# ProDocument_Original_2023-07-23.net
KiCad netlist of a schematic drawn in EasyEDA Pro
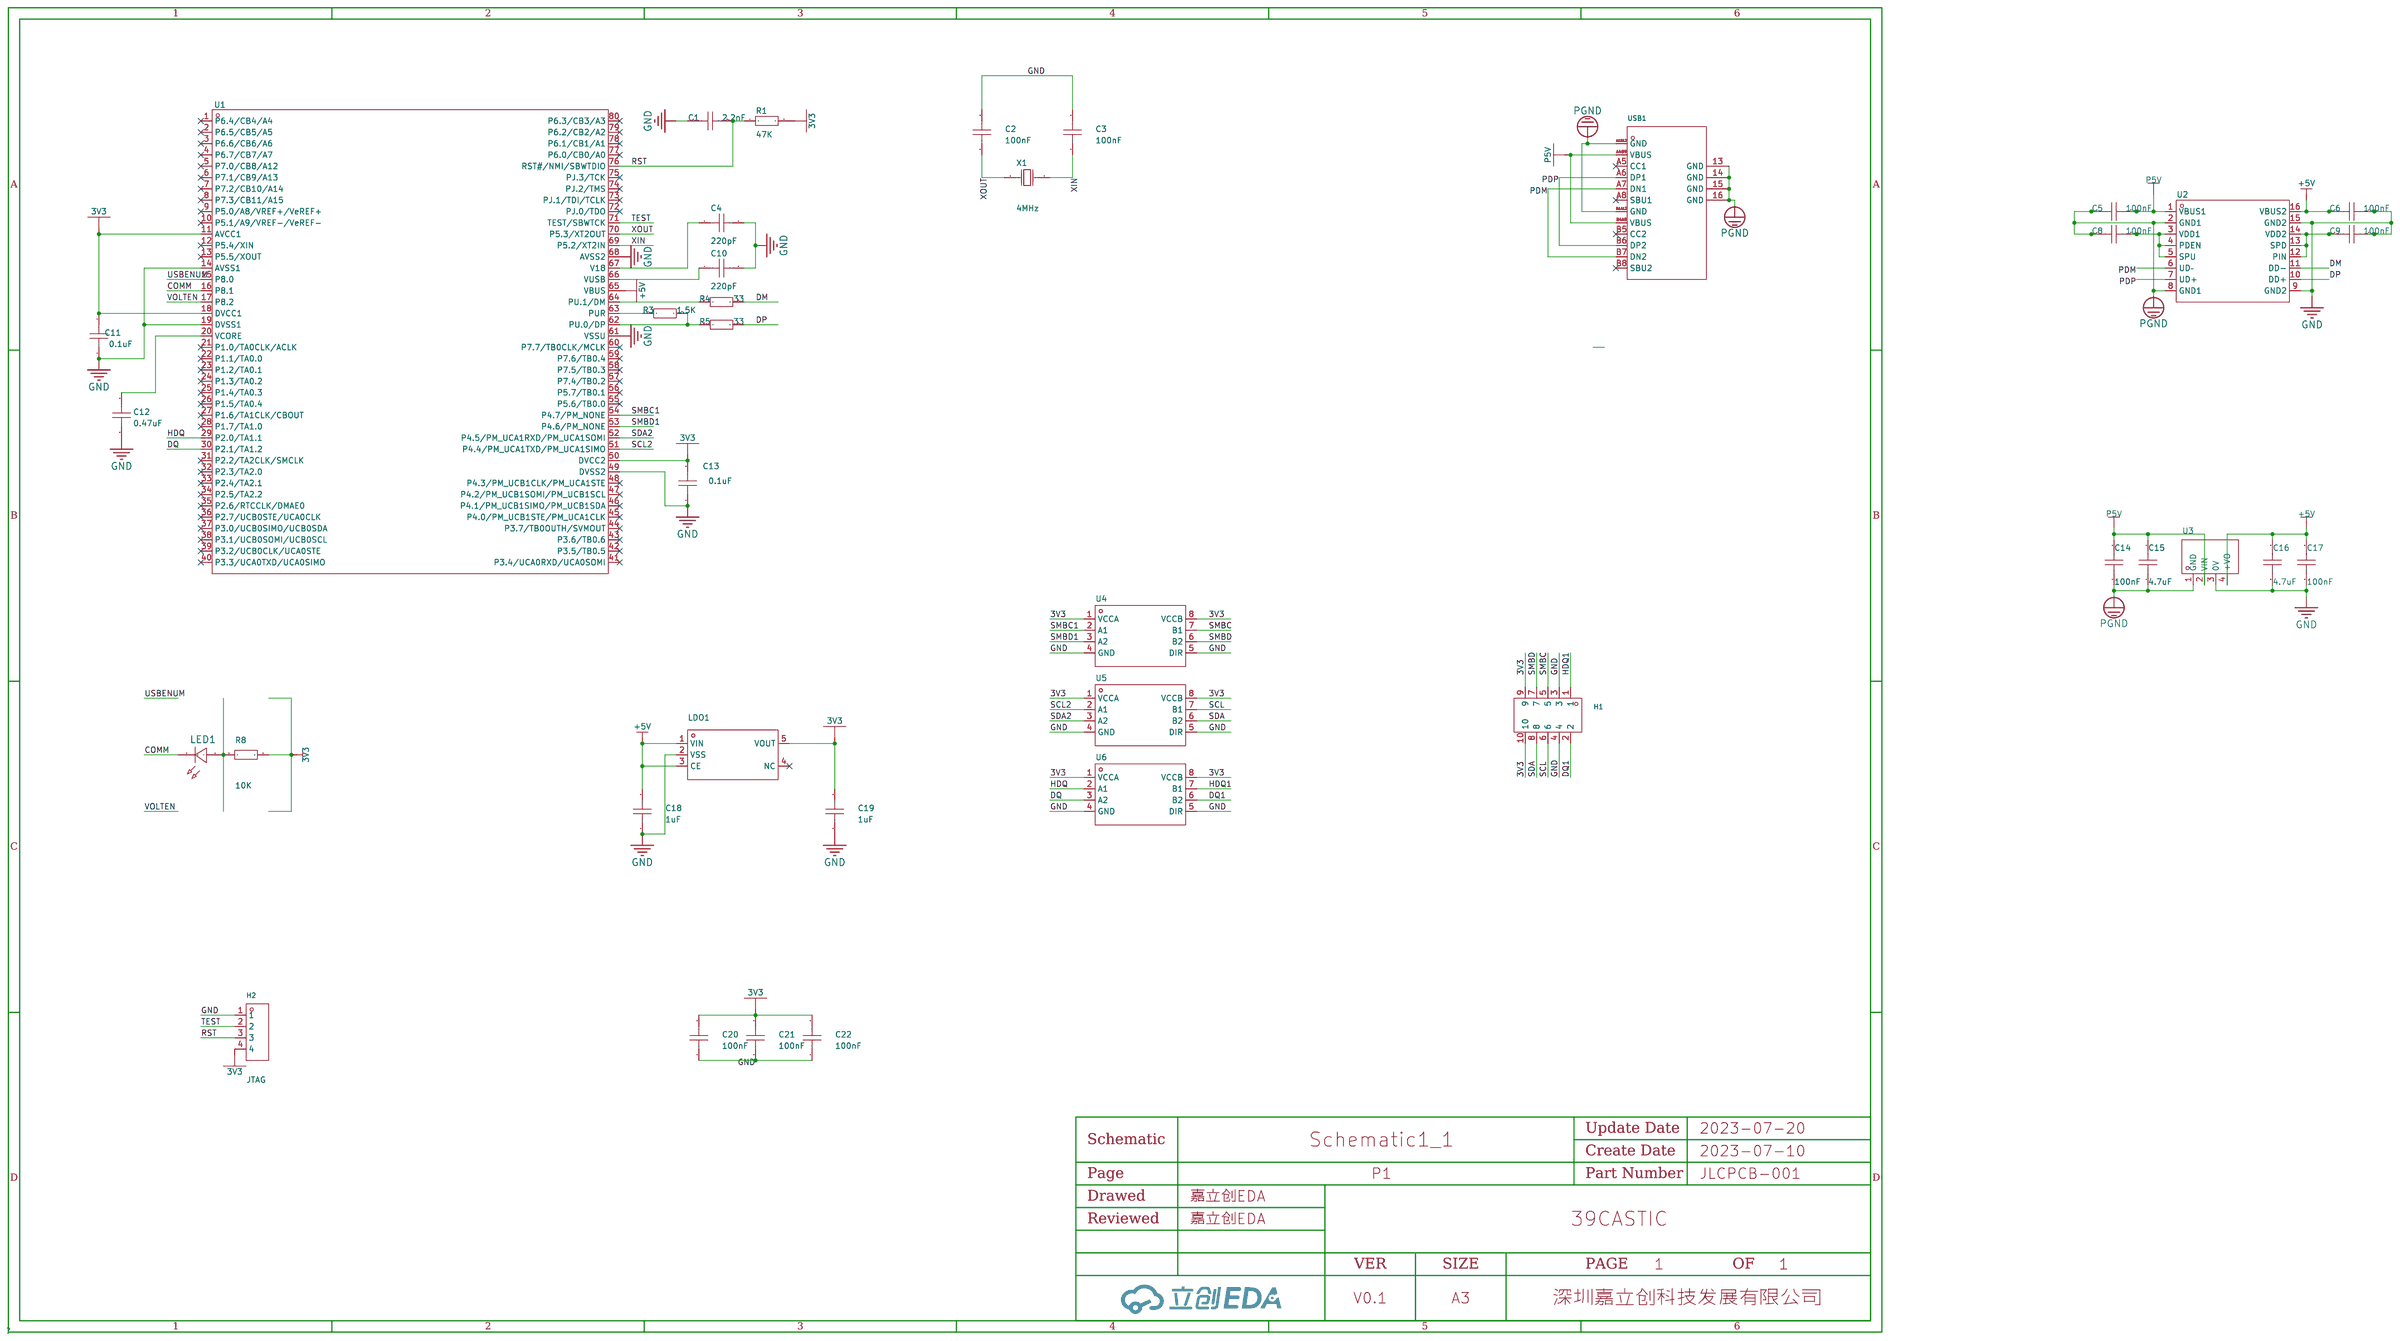
[diagram p0: schematic sheet]

(export (version "E")
  (design (tool "Eeschema 10.0.6"))
  (components
    (comp (ref "C1")
      (value "2.2nF")
      (footprint "easyedapro:C0603_1")
      (description "容值:100nF;精度:±10%;额定电压:50V;温度系数:X7R;")
      (libsource (lib "easyedapro") (part "C1210X7R475K630NT"))
    )
    (comp (ref "C2")
      (value "100nF")
      (footprint "easyedapro:C0603")
      (libsource (lib "easyedapro") (part "CapAcitance"))
    )
    (comp (ref "C3")
      (value "100nF")
      (footprint "easyedapro:C0603")
      (libsource (lib "easyedapro") (part "CapAcitance"))
    )
    (comp (ref "C4")
      (value "220pF")
      (footprint "easyedapro:C0603_1")
      (description "容值:100nF;精度:±10%;额定电压:50V;温度系数:X7R;")
      (libsource (lib "easyedapro") (part "C1210X7R475K630NT"))
    )
    (comp (ref "C5")
      (value "100nF")
      (footprint "easyedapro:C0603")
      (libsource (lib "easyedapro") (part "CapAcitance"))
    )
    (comp (ref "C6")
      (value "100nF")
      (footprint "easyedapro:C0603")
      (libsource (lib "easyedapro") (part "CapAcitance"))
    )
    (comp (ref "C8")
      (value "100nF")
      (footprint "easyedapro:C0603")
      (libsource (lib "easyedapro") (part "CapAcitance"))
    )
    (comp (ref "C9")
      (value "100nF")
      (footprint "easyedapro:C0603")
      (libsource (lib "easyedapro") (part "CapAcitance"))
    )
    (comp (ref "C10")
      (value "220pF")
      (footprint "easyedapro:C0603_1")
      (description "容值:100nF;精度:±10%;额定电压:50V;温度系数:X7R;")
      (libsource (lib "easyedapro") (part "C1210X7R475K630NT"))
    )
    (comp (ref "C11")
      (value "0.1uF")
      (footprint "easyedapro:C0603_1")
      (description "容值:100nF;精度:±10%;额定电压:50V;温度系数:X7R;")
      (libsource (lib "easyedapro") (part "C1210X7R475K630NT"))
    )
    (comp (ref "C12")
      (value "0.47uF")
      (footprint "easyedapro:C0603_1")
      (description "容值:100nF;精度:±10%;额定电压:50V;温度系数:X7R;")
      (libsource (lib "easyedapro") (part "C1210X7R475K630NT"))
    )
    (comp (ref "C13")
      (value "0.1uF")
      (footprint "easyedapro:C0603_1")
      (description "容值:100nF;精度:±10%;额定电压:50V;温度系数:X7R;")
      (libsource (lib "easyedapro") (part "C1210X7R475K630NT"))
    )
    (comp (ref "C14")
      (value "100nF")
      (footprint "easyedapro:C0603")
      (libsource (lib "easyedapro") (part "CapAcitance"))
    )
    (comp (ref "C15")
      (value "4.7uF")
      (footprint "easyedapro:C0603")
      (libsource (lib "easyedapro") (part "CapAcitance"))
    )
    (comp (ref "C16")
      (value "4.7uF")
      (footprint "easyedapro:C0603")
      (libsource (lib "easyedapro") (part "CapAcitance"))
    )
    (comp (ref "C17")
      (value "100nF")
      (footprint "easyedapro:C0603")
      (libsource (lib "easyedapro") (part "CapAcitance"))
    )
    (comp (ref "C18")
      (value "1uF")
      (footprint "easyedapro:C0603")
      (libsource (lib "easyedapro") (part "CapAcitance"))
    )
    (comp (ref "C19")
      (value "1uF")
      (footprint "easyedapro:C0603")
      (libsource (lib "easyedapro") (part "CapAcitance"))
    )
    (comp (ref "C20")
      (value "100nF")
      (footprint "easyedapro:C0603")
      (libsource (lib "easyedapro") (part "CapAcitance"))
    )
    (comp (ref "C21")
      (value "100nF")
      (footprint "easyedapro:C0603")
      (libsource (lib "easyedapro") (part "CapAcitance"))
    )
    (comp (ref "C22")
      (value "100nF")
      (footprint "easyedapro:C0603")
      (libsource (lib "easyedapro") (part "CapAcitance"))
    )
    (comp (ref "H1")
      (value "PZ254V-12-10P")
      (footprint "easyedapro:HDR-TH_10P-P2.54-V-M-R2-C5-S2.54")
      (fields (field (name "Manufacturer") "XFCN(兴飞)"))
      (libsource (lib "easyedapro") (part "PZ254V-12-10P"))
    )
    (comp (ref "H2")
      (value "JTAG")
      (footprint "easyedapro:HDR-TH_4P-P2.54-V-F")
      (libsource (lib "easyedapro") (part "2.54-1*4P母"))
    )
    (comp (ref "LDO1")
      (value "ME6211C33M5G-N")
      (footprint "easyedapro:SOT-23-5_L3.0-W1.7-P0.95-LS2.8-BL")
      (description "输出类型:固定;输出极性:正;最大输入电压:6V;输出电压:3.3V;输出电流:500mA;电源纹波抑制比(PSRR):70dB;")
      (fields (field (name "Manufacturer") "MICRONE(南京微盟)"))
      (libsource (lib "easyedapro") (part "ME6211C33M5G-N"))
    )
    (comp (ref "LED1")
      (value "~")
      (footprint "easyedapro:LED_0603")
      (libsource (lib "easyedapro") (part "LED_R"))
    )
    (comp (ref "R1")
      (value "47K")
      (footprint "easyedapro:R0603_1")
      (libsource (lib "easyedapro") (part "电阻_1"))
    )
    (comp (ref "R3")
      (value "1.5K")
      (footprint "easyedapro:R0603_1")
      (libsource (lib "easyedapro") (part "电阻_1"))
    )
    (comp (ref "R4")
      (value "33")
      (footprint "easyedapro:R0603_1")
      (libsource (lib "easyedapro") (part "电阻_1"))
    )
    (comp (ref "R5")
      (value "33")
      (footprint "easyedapro:R0603_1")
      (libsource (lib "easyedapro") (part "电阻_1"))
    )
    (comp (ref "R8") (value "10K") (footprint "easyedapro:R0603") (libsource (lib "easyedapro") (part "电阻")))
    (comp (ref "U1")
      (value "~")
      (footprint "easyedapro:LQFP-80_L12.0-W12.0-P0.50-LS14.0-BL")
      (description "CPU位数:-;ROM类型:-;CPU内核:-;主频（MAX):-;工作电压:-;")
      (fields (field (name "Manufacturer Part") "MSP430F5529IPN") (field (name "Manufacturer") "TI(德州仪器)"))
      (libsource (lib "easyedapro") (part "MSP430F5529IPN"))
    )
    (comp (ref "U2")
      (value "ADUM3160BRWZ-RL")
      (footprint "easyedapro:SOIC-16_L10.3-W7.5-P1.27-LS10.3-BL")
      (description "隔离器的技术构架:-;类型:-;通道数:-;通道类型:-;隔离电压:-;数据速率:-;")
      (fields (field (name "Manufacturer") "ADI(亚德诺)/LINEAR(凌特)"))
      (libsource (lib "easyedapro") (part "ADUM3160BRWZ-RL"))
    )
    (comp (ref "U3")
      (value "B0505S-1W")
      (footprint "easyedapro:PWRM-TH_B0505S-1W")
      (description "电压输出的组数:1;最大输入电压:5.5V;输出电压:5V;输出电流（最大值/满载）:200mA;")
      (fields (field (name "Manufacturer") "德旭电子(DEXU)"))
      (libsource (lib "easyedapro") (part "B0505S-1W_C2912568"))
    )
    (comp (ref "U4")
      (value "SN74LVC2T45DCUR")
      (footprint "easyedapro:VSSOP-8_L2.4-W2.1-P0.50-LS3.2-BR")
      (description "SN74LVC2T45 具有可配置电压转换和三态输出的 2 位双电源总线收发器")
      (fields (field (name "Manufacturer") "TI(德州仪器)"))
      (libsource (lib "easyedapro") (part "SN74LVC2T45DCUR"))
    )
    (comp (ref "U5")
      (value "SN74LVC2T45DCUR")
      (footprint "easyedapro:VSSOP-8_L2.4-W2.1-P0.50-LS3.2-BR")
      (description "SN74LVC2T45 具有可配置电压转换和三态输出的 2 位双电源总线收发器")
      (fields (field (name "Manufacturer") "TI(德州仪器)"))
      (libsource (lib "easyedapro") (part "SN74LVC2T45DCUR"))
    )
    (comp (ref "U6")
      (value "SN74LVC2T45DCUR")
      (footprint "easyedapro:VSSOP-8_L2.4-W2.1-P0.50-LS3.2-BR")
      (description "SN74LVC2T45 具有可配置电压转换和三态输出的 2 位双电源总线收发器")
      (fields (field (name "Manufacturer") "TI(德州仪器)"))
      (libsource (lib "easyedapro") (part "SN74LVC2T45DCUR"))
    )
    (comp (ref "USB1")
      (value "TYPEC-304-BCP16")
      (footprint "easyedapro:USB-C-SMD_TYPEC-304-BCP16")
      (fields (field (name "Manufacturer") "XUNPU(讯普)"))
      (libsource (lib "easyedapro") (part "TYPEC-304-BCP16"))
    )
    (comp (ref "X1")
      (value "4MHz")
      (footprint "easyedapro:HC-49US_L11.5-W4.5-P4.88")
      (description "频率:4MHz;频率公差:±20ppm;负载电容:20pF;")
      (fields (field (name "Manufacturer Part") "X49SD4MSD2SC") (field (name "Manufacturer") "YXC(扬兴晶振)"))
      (libsource (lib "easyedapro") (part "X49SD4MSD2SC"))
    )
  )
  (nets
    (net (code "1") (name "+5V") (class "Default")
      (node (ref "C16") (pin "2") (pinfunction "2_2") (pintype "input"))
      (node (ref "C17") (pin "2") (pinfunction "2_2") (pintype "input"))
      (node (ref "C18") (pin "2") (pinfunction "2_2") (pintype "input"))
      (node (ref "C6") (pin "1") (pinfunction "1_1") (pintype "input"))
      (node (ref "LDO1") (pin "1") (pinfunction "VIN_1") (pintype "input"))
      (node (ref "LDO1") (pin "3") (pinfunction "CE_3") (pintype "input"))
      (node (ref "U1") (pin "65") (pinfunction "VBUS_65") (pintype "input"))
      (node (ref "U2") (pin "16") (pinfunction "VBUS2_16") (pintype "input"))
      (node (ref "U3") (pin "4") (pinfunction "+VO_4") (pintype "input"))
    )
    (net (code "2") (name "/COMM") (class "Default")
      (node (ref "LED1") (pin "1") (pinfunction "C_1") (pintype "input"))
      (node (ref "U1") (pin "16") (pinfunction "P8.1_16") (pintype "input"))
    )
    (net (code "3") (name "/DM") (class "Default")
      (node (ref "R4") (pin "2") (pinfunction "2_2") (pintype "input"))
      (node (ref "U2") (pin "11") (pinfunction "DD-_11") (pintype "input"))
    )
    (net (code "4") (name "/DP") (class "Default")
      (node (ref "R5") (pin "2") (pinfunction "2_2") (pintype "input"))
      (node (ref "U2") (pin "10") (pinfunction "DD+_10") (pintype "input"))
    )
    (net (code "5") (name "/DQ") (class "Default")
      (node (ref "U1") (pin "30") (pinfunction "P2.1/TA1.2_30") (pintype "input"))
      (node (ref "U6") (pin "3") (pinfunction "A2_3") (pintype "input"))
    )
    (net (code "6") (name "/DQ1") (class "Default")
      (node (ref "H1") (pin "2") (pinfunction "2_2") (pintype "input"))
      (node (ref "U6") (pin "6") (pinfunction "B2_6") (pintype "input"))
    )
    (net (code "7") (name "/HDQ") (class "Default")
      (node (ref "U1") (pin "29") (pinfunction "P2.0/TA1.1_29") (pintype "input"))
      (node (ref "U6") (pin "2") (pinfunction "A1_2") (pintype "input"))
    )
    (net (code "8") (name "/HDQ1") (class "Default")
      (node (ref "H1") (pin "1") (pinfunction "1_1") (pintype "input"))
      (node (ref "U6") (pin "7") (pinfunction "B1_7") (pintype "input"))
    )
    (net (code "9") (name "/PDM") (class "Default")
      (node (ref "U2") (pin "6") (pinfunction "UD–_6") (pintype "input"))
      (node (ref "USB1") (pin "A7") (pinfunction "DN1_A7") (pintype "input"))
      (node (ref "USB1") (pin "B7") (pinfunction "DN2_B7") (pintype "input"))
    )
    (net (code "10") (name "/PDP") (class "Default")
      (node (ref "U2") (pin "7") (pinfunction "UD+_7") (pintype "input"))
      (node (ref "USB1") (pin "A6") (pinfunction "DP1_A6") (pintype "input"))
      (node (ref "USB1") (pin "B6") (pinfunction "DP2_B6") (pintype "input"))
    )
    (net (code "11") (name "/RST") (class "Default")
      (node (ref "C1") (pin "2") (pinfunction "2_2") (pintype "input"))
      (node (ref "H2") (pin "3") (pinfunction "3_3") (pintype "input"))
      (node (ref "R1") (pin "1") (pinfunction "1_1") (pintype "input"))
      (node (ref "U1") (pin "76") (pinfunction "RST#/NMI/SBWTDIO_76") (pintype "input"))
    )
    (net (code "12") (name "/SCL") (class "Default")
      (node (ref "H1") (pin "6") (pinfunction "6_6") (pintype "input"))
      (node (ref "U5") (pin "7") (pinfunction "B1_7") (pintype "input"))
    )
    (net (code "13") (name "/SCL2") (class "Default")
      (node (ref "U1") (pin "51") (pinfunction "P4.4/PM_UCA1TXD/PM_UCA1SIMO_51") (pintype "input"))
      (node (ref "U5") (pin "2") (pinfunction "A1_2") (pintype "input"))
    )
    (net (code "14") (name "/SDA") (class "Default")
      (node (ref "H1") (pin "8") (pinfunction "8_8") (pintype "input"))
      (node (ref "U5") (pin "6") (pinfunction "B2_6") (pintype "input"))
    )
    (net (code "15") (name "/SDA2") (class "Default")
      (node (ref "U1") (pin "52") (pinfunction "P4.5/PM_UCA1RXD/PM_UCA1SOMI_52") (pintype "input"))
      (node (ref "U5") (pin "3") (pinfunction "A2_3") (pintype "input"))
    )
    (net (code "16") (name "/SMBC") (class "Default")
      (node (ref "H1") (pin "5") (pinfunction "5_5") (pintype "input"))
      (node (ref "U4") (pin "7") (pinfunction "B1_7") (pintype "input"))
    )
    (net (code "17") (name "/SMBC1") (class "Default")
      (node (ref "U1") (pin "54") (pinfunction "P4.7/PM_NONE_54") (pintype "input"))
      (node (ref "U4") (pin "2") (pinfunction "A1_2") (pintype "input"))
    )
    (net (code "18") (name "/SMBD") (class "Default")
      (node (ref "H1") (pin "7") (pinfunction "7_7") (pintype "input"))
      (node (ref "U4") (pin "6") (pinfunction "B2_6") (pintype "input"))
    )
    (net (code "19") (name "/SMBD1") (class "Default")
      (node (ref "U1") (pin "53") (pinfunction "P4.6/PM_NONE_53") (pintype "input"))
      (node (ref "U4") (pin "3") (pinfunction "A2_3") (pintype "input"))
    )
    (net (code "20") (name "/TEST") (class "Default")
      (node (ref "H2") (pin "2") (pinfunction "2_2") (pintype "input"))
      (node (ref "U1") (pin "71") (pinfunction "TEST/SBWTCK_71") (pintype "input"))
    )
    (net (code "21") (name "/USBENUM") (class "Default")
      (node (ref "U1") (pin "15") (pinfunction "P8.0_15") (pintype "input"))
    )
    (net (code "22") (name "/VOLTEN") (class "Default")
      (node (ref "U1") (pin "17") (pinfunction "P8.2_17") (pintype "input"))
    )
    (net (code "23") (name "/XIN") (class "Default")
      (node (ref "C3") (pin "1") (pinfunction "1_1") (pintype "input"))
      (node (ref "U1") (pin "69") (pinfunction "P5.2/XT2IN_69") (pintype "input"))
      (node (ref "X1") (pin "1") (pinfunction "OSC1_1") (pintype "input"))
    )
    (net (code "24") (name "/XOUT") (class "Default")
      (node (ref "C2") (pin "1") (pinfunction "1_1") (pintype "input"))
      (node (ref "U1") (pin "70") (pinfunction "P5.3/XT2OUT_70") (pintype "input"))
      (node (ref "X1") (pin "2") (pinfunction "OSC2_2") (pintype "input"))
    )
    (net (code "25") (name "3V3") (class "Default")
      (node (ref "C11") (pin "2") (pinfunction "2_2") (pintype "input"))
      (node (ref "C13") (pin "2") (pinfunction "2_2") (pintype "input"))
      (node (ref "C19") (pin "2") (pinfunction "2_2") (pintype "input"))
      (node (ref "C20") (pin "2") (pinfunction "2_2") (pintype "input"))
      (node (ref "C21") (pin "2") (pinfunction "2_2") (pintype "input"))
      (node (ref "C22") (pin "2") (pinfunction "2_2") (pintype "input"))
      (node (ref "H1") (pin "10") (pinfunction "10_10") (pintype "input"))
      (node (ref "H1") (pin "9") (pinfunction "9_9") (pintype "input"))
      (node (ref "H2") (pin "4") (pinfunction "4_4") (pintype "input"))
      (node (ref "LDO1") (pin "5") (pinfunction "VOUT_5") (pintype "input"))
      (node (ref "R1") (pin "2") (pinfunction "2_2") (pintype "input"))
      (node (ref "R8") (pin "2") (pinfunction "2_2") (pintype "input"))
      (node (ref "U1") (pin "11") (pinfunction "AVCC1_11") (pintype "input"))
      (node (ref "U1") (pin "18") (pinfunction "DVCC1_18") (pintype "input"))
      (node (ref "U1") (pin "50") (pinfunction "DVCC2_50") (pintype "input"))
      (node (ref "U4") (pin "1") (pinfunction "VCCA_1") (pintype "input"))
      (node (ref "U4") (pin "8") (pinfunction "VCCB_8") (pintype "input"))
      (node (ref "U5") (pin "1") (pinfunction "VCCA_1") (pintype "input"))
      (node (ref "U5") (pin "8") (pinfunction "VCCB_8") (pintype "input"))
      (node (ref "U6") (pin "1") (pinfunction "VCCA_1") (pintype "input"))
      (node (ref "U6") (pin "8") (pinfunction "VCCB_8") (pintype "input"))
    )
    (net (code "26") (name "GND") (class "Default")
      (node (ref "C1") (pin "1") (pinfunction "1_1") (pintype "input"))
      (node (ref "C10") (pin "2") (pinfunction "2_2") (pintype "input"))
      (node (ref "C11") (pin "1") (pinfunction "1_1") (pintype "input"))
      (node (ref "C12") (pin "1") (pinfunction "1_1") (pintype "input"))
      (node (ref "C13") (pin "1") (pinfunction "1_1") (pintype "input"))
      (node (ref "C16") (pin "1") (pinfunction "1_1") (pintype "input"))
      (node (ref "C17") (pin "1") (pinfunction "1_1") (pintype "input"))
      (node (ref "C18") (pin "1") (pinfunction "1_1") (pintype "input"))
      (node (ref "C19") (pin "1") (pinfunction "1_1") (pintype "input"))
      (node (ref "C2") (pin "2") (pinfunction "2_2") (pintype "input"))
      (node (ref "C20") (pin "1") (pinfunction "1_1") (pintype "input"))
      (node (ref "C21") (pin "1") (pinfunction "1_1") (pintype "input"))
      (node (ref "C22") (pin "1") (pinfunction "1_1") (pintype "input"))
      (node (ref "C3") (pin "2") (pinfunction "2_2") (pintype "input"))
      (node (ref "C4") (pin "2") (pinfunction "2_2") (pintype "input"))
      (node (ref "C6") (pin "2") (pinfunction "2_2") (pintype "input"))
      (node (ref "C9") (pin "2") (pinfunction "2_2") (pintype "input"))
      (node (ref "H1") (pin "3") (pinfunction "3_3") (pintype "input"))
      (node (ref "H1") (pin "4") (pinfunction "4_4") (pintype "input"))
      (node (ref "H2") (pin "1") (pinfunction "1_1") (pintype "input"))
      (node (ref "LDO1") (pin "2") (pinfunction "VSS_2") (pintype "input"))
      (node (ref "U1") (pin "14") (pinfunction "AVSS1_14") (pintype "input"))
      (node (ref "U1") (pin "19") (pinfunction "DVSS1_19") (pintype "input"))
      (node (ref "U1") (pin "49") (pinfunction "DVSS2_49") (pintype "input"))
      (node (ref "U1") (pin "61") (pinfunction "VSSU_61") (pintype "input"))
      (node (ref "U1") (pin "68") (pinfunction "AVSS2_68") (pintype "input"))
      (node (ref "U2") (pin "15") (pinfunction "GND2_15") (pintype "input"))
      (node (ref "U2") (pin "9") (pinfunction "GND2_9") (pintype "input"))
      (node (ref "U3") (pin "3") (pinfunction "0V_3") (pintype "input"))
      (node (ref "U4") (pin "4") (pinfunction "GND_4") (pintype "input"))
      (node (ref "U4") (pin "5") (pinfunction "DIR_5") (pintype "input"))
      (node (ref "U5") (pin "4") (pinfunction "GND_4") (pintype "input"))
      (node (ref "U5") (pin "5") (pinfunction "DIR_5") (pintype "input"))
      (node (ref "U6") (pin "4") (pinfunction "GND_4") (pintype "input"))
      (node (ref "U6") (pin "5") (pinfunction "DIR_5") (pintype "input"))
    )
    (net (code "27") (name "Net-(LED1-A)") (class "Default")
      (node (ref "LED1") (pin "2") (pinfunction "A_2") (pintype "input"))
      (node (ref "R8") (pin "1") (pinfunction "1_1") (pintype "input"))
    )
    (net (code "28") (name "Net-(U1-PU.0{slash}DP)") (class "Default")
      (node (ref "R3") (pin "2") (pinfunction "2_2") (pintype "input"))
      (node (ref "R5") (pin "1") (pinfunction "1_1") (pintype "input"))
      (node (ref "U1") (pin "62") (pinfunction "PU.0/DP_62") (pintype "input"))
    )
    (net (code "29") (name "Net-(U1-PU.1{slash}DM)") (class "Default")
      (node (ref "R4") (pin "1") (pinfunction "1_1") (pintype "input"))
      (node (ref "U1") (pin "64") (pinfunction "PU.1/DM_64") (pintype "input"))
    )
    (net (code "30") (name "Net-(U1-PUR)") (class "Default")
      (node (ref "R3") (pin "1") (pinfunction "1_1") (pintype "input"))
      (node (ref "U1") (pin "63") (pinfunction "PUR_63") (pintype "input"))
    )
    (net (code "31") (name "Net-(U1-V18)") (class "Default")
      (node (ref "C4") (pin "1") (pinfunction "1_1") (pintype "input"))
      (node (ref "U1") (pin "67") (pinfunction "V18_67") (pintype "input"))
    )
    (net (code "32") (name "Net-(U1-VCORE)") (class "Default")
      (node (ref "C12") (pin "2") (pinfunction "2_2") (pintype "input"))
      (node (ref "U1") (pin "20") (pinfunction "VCORE_20") (pintype "input"))
    )
    (net (code "33") (name "Net-(U1-VUSB)") (class "Default")
      (node (ref "C10") (pin "1") (pinfunction "1_1") (pintype "input"))
      (node (ref "U1") (pin "66") (pinfunction "VUSB_66") (pintype "input"))
    )
    (net (code "34") (name "Net-(U2-PDEN)") (class "Default")
      (node (ref "C8") (pin "2") (pinfunction "2_2") (pintype "input"))
      (node (ref "U2") (pin "3") (pinfunction "VDD1_3") (pintype "input"))
      (node (ref "U2") (pin "4") (pinfunction "PDEN_4") (pintype "input"))
      (node (ref "U2") (pin "5") (pinfunction "SPU_5") (pintype "input"))
    )
    (net (code "35") (name "Net-(U2-PIN)") (class "Default")
      (node (ref "C9") (pin "1") (pinfunction "1_1") (pintype "input"))
      (node (ref "U2") (pin "12") (pinfunction "PIN_12") (pintype "input"))
      (node (ref "U2") (pin "13") (pinfunction "SPD_13") (pintype "input"))
      (node (ref "U2") (pin "14") (pinfunction "VDD2_14") (pintype "input"))
    )
    (net (code "36") (name "P5V") (class "Default")
      (node (ref "C14") (pin "2") (pinfunction "2_2") (pintype "input"))
      (node (ref "C15") (pin "2") (pinfunction "2_2") (pintype "input"))
      (node (ref "C5") (pin "2") (pinfunction "2_2") (pintype "input"))
      (node (ref "U2") (pin "1") (pinfunction "VBUS1_1") (pintype "input"))
      (node (ref "U3") (pin "2") (pinfunction "VIN_2") (pintype "input"))
      (node (ref "USB1") (pin "A4B9") (pinfunction "VBUS_A4B9") (pintype "input"))
      (node (ref "USB1") (pin "B4A9") (pinfunction "VBUS_B4A9") (pintype "input"))
    )
    (net (code "37") (name "PGND") (class "Default")
      (node (ref "C14") (pin "1") (pinfunction "1_1") (pintype "input"))
      (node (ref "C15") (pin "1") (pinfunction "1_1") (pintype "input"))
      (node (ref "C5") (pin "1") (pinfunction "1_1") (pintype "input"))
      (node (ref "C8") (pin "1") (pinfunction "1_1") (pintype "input"))
      (node (ref "U2") (pin "2") (pinfunction "GND1_2") (pintype "input"))
      (node (ref "U2") (pin "8") (pinfunction "GND1_8") (pintype "input"))
      (node (ref "U3") (pin "1") (pinfunction "GND_1") (pintype "input"))
      (node (ref "USB1") (pin "13") (pinfunction "GND_13") (pintype "input"))
      (node (ref "USB1") (pin "14") (pinfunction "GND_14") (pintype "input"))
      (node (ref "USB1") (pin "15") (pinfunction "GND_15") (pintype "input"))
      (node (ref "USB1") (pin "16") (pinfunction "GND_16") (pintype "input"))
      (node (ref "USB1") (pin "A1B12") (pinfunction "GND_A1B12") (pintype "input"))
      (node (ref "USB1") (pin "B1A12") (pinfunction "GND_B1A12") (pintype "input"))
    )
    (net (code "38") (name "unconnected-(LDO1-NC-Pad4)") (class "Default")
      (node (ref "LDO1") (pin "4") (pinfunction "NC_4") (pintype "input+no_connect"))
    )
    (net (code "39") (name "unconnected-(U1-P1.0{slash}TA0CLK{slash}ACLK-Pad21)") (class "Default")
      (node (ref "U1") (pin "21") (pinfunction "P1.0/TA0CLK/ACLK_21") (pintype "input+no_connect"))
    )
    (net (code "40") (name "unconnected-(U1-P1.1{slash}TA0.0-Pad22)") (class "Default")
      (node (ref "U1") (pin "22") (pinfunction "P1.1/TA0.0_22") (pintype "input+no_connect"))
    )
    (net (code "41") (name "unconnected-(U1-P1.2{slash}TA0.1-Pad23)") (class "Default")
      (node (ref "U1") (pin "23") (pinfunction "P1.2/TA0.1_23") (pintype "input+no_connect"))
    )
    (net (code "42") (name "unconnected-(U1-P1.3{slash}TA0.2-Pad24)") (class "Default")
      (node (ref "U1") (pin "24") (pinfunction "P1.3/TA0.2_24") (pintype "input+no_connect"))
    )
    (net (code "43") (name "unconnected-(U1-P1.4{slash}TA0.3-Pad25)") (class "Default")
      (node (ref "U1") (pin "25") (pinfunction "P1.4/TA0.3_25") (pintype "input+no_connect"))
    )
    (net (code "44") (name "unconnected-(U1-P1.5{slash}TA0.4-Pad26)") (class "Default")
      (node (ref "U1") (pin "26") (pinfunction "P1.5/TA0.4_26") (pintype "input+no_connect"))
    )
    (net (code "45") (name "unconnected-(U1-P1.6{slash}TA1CLK{slash}CBOUT-Pad27)") (class "Default")
      (node (ref "U1") (pin "27") (pinfunction "P1.6/TA1CLK/CBOUT_27") (pintype "input+no_connect"))
    )
    (net (code "46") (name "unconnected-(U1-P1.7{slash}TA1.0-Pad28)") (class "Default")
      (node (ref "U1") (pin "28") (pinfunction "P1.7/TA1.0_28") (pintype "input+no_connect"))
    )
    (net (code "47") (name "unconnected-(U1-P2.2{slash}TA2CLK{slash}SMCLK-Pad31)") (class "Default")
      (node (ref "U1") (pin "31") (pinfunction "P2.2/TA2CLK/SMCLK_31") (pintype "input+no_connect"))
    )
    (net (code "48") (name "unconnected-(U1-P2.3{slash}TA2.0-Pad32)") (class "Default")
      (node (ref "U1") (pin "32") (pinfunction "P2.3/TA2.0_32") (pintype "input+no_connect"))
    )
    (net (code "49") (name "unconnected-(U1-P2.4{slash}TA2.1-Pad33)") (class "Default")
      (node (ref "U1") (pin "33") (pinfunction "P2.4/TA2.1_33") (pintype "input+no_connect"))
    )
    (net (code "50") (name "unconnected-(U1-P2.5{slash}TA2.2-Pad34)") (class "Default")
      (node (ref "U1") (pin "34") (pinfunction "P2.5/TA2.2_34") (pintype "input+no_connect"))
    )
    (net (code "51") (name "unconnected-(U1-P2.6{slash}RTCCLK{slash}DMAE0-Pad35)") (class "Default")
      (node (ref "U1") (pin "35") (pinfunction "P2.6/RTCCLK/DMAE0_35") (pintype "input+no_connect"))
    )
    (net (code "52") (name "unconnected-(U1-P2.7{slash}UCB0STE{slash}UCA0CLK-Pad36)") (class "Default")
      (node (ref "U1") (pin "36") (pinfunction "P2.7/UCB0STE/UCA0CLK_36") (pintype "input+no_connect"))
    )
    (net (code "53") (name "unconnected-(U1-P3.0{slash}UCB0SIMO{slash}UCB0SDA-Pad37)") (class "Default")
      (node (ref "U1") (pin "37") (pinfunction "P3.0/UCB0SIMO/UCB0SDA_37") (pintype "input+no_connect"))
    )
    (net (code "54") (name "unconnected-(U1-P3.1{slash}UCB0SOMI{slash}UCB0SCL-Pad38)") (class "Default")
      (node (ref "U1") (pin "38") (pinfunction "P3.1/UCB0SOMI/UCB0SCL_38") (pintype "input+no_connect"))
    )
    (net (code "55") (name "unconnected-(U1-P3.2{slash}UCB0CLK{slash}UCA0STE-Pad39)") (class "Default")
      (node (ref "U1") (pin "39") (pinfunction "P3.2/UCB0CLK/UCA0STE_39") (pintype "input+no_connect"))
    )
    (net (code "56") (name "unconnected-(U1-P3.3{slash}UCA0TXD{slash}UCA0SIMO-Pad40)") (class "Default")
      (node (ref "U1") (pin "40") (pinfunction "P3.3/UCA0TXD/UCA0SIMO_40") (pintype "input+no_connect"))
    )
    (net (code "57") (name "unconnected-(U1-P3.4{slash}UCA0RXD{slash}UCA0SOMI-Pad41)") (class "Default")
      (node (ref "U1") (pin "41") (pinfunction "P3.4/UCA0RXD/UCA0SOMI_41") (pintype "input+no_connect"))
    )
    (net (code "58") (name "unconnected-(U1-P3.5{slash}TB0.5-Pad42)") (class "Default")
      (node (ref "U1") (pin "42") (pinfunction "P3.5/TB0.5_42") (pintype "input+no_connect"))
    )
    (net (code "59") (name "unconnected-(U1-P3.6{slash}TB0.6-Pad43)") (class "Default")
      (node (ref "U1") (pin "43") (pinfunction "P3.6/TB0.6_43") (pintype "input+no_connect"))
    )
    (net (code "60") (name "unconnected-(U1-P3.7{slash}TB0OUTH{slash}SVMOUT-Pad44)") (class "Default")
      (node (ref "U1") (pin "44") (pinfunction "P3.7/TB0OUTH/SVMOUT_44") (pintype "input+no_connect"))
    )
    (net (code "61") (name "unconnected-(U1-P4.0{slash}PM_UCB1STE{slash}PM_UCA1CLK-Pad45)") (class "Default")
      (node (ref "U1") (pin "45") (pinfunction "P4.0/PM_UCB1STE/PM_UCA1CLK_45") (pintype "input+no_connect"))
    )
    (net (code "62") (name "unconnected-(U1-P4.1{slash}PM_UCB1SIMO{slash}PM_UCB1SDA-Pad46)") (class "Default")
      (node (ref "U1") (pin "46") (pinfunction "P4.1/PM_UCB1SIMO/PM_UCB1SDA_46") (pintype "input+no_connect"))
    )
    (net (code "63") (name "unconnected-(U1-P4.2{slash}PM_UCB1SOMI{slash}PM_UCB1SCL-Pad47)") (class "Default")
      (node (ref "U1") (pin "47") (pinfunction "P4.2/PM_UCB1SOMI/PM_UCB1SCL_47") (pintype "input+no_connect"))
    )
    (net (code "64") (name "unconnected-(U1-P4.3{slash}PM_UCB1CLK{slash}PM_UCA1STE-Pad48)") (class "Default")
      (node (ref "U1") (pin "48") (pinfunction "P4.3/PM_UCB1CLK/PM_UCA1STE_48") (pintype "input+no_connect"))
    )
    (net (code "65") (name "unconnected-(U1-P5.0{slash}A8{slash}VREF+{slash}VeREF+-Pad9)") (class "Default")
      (node (ref "U1") (pin "9") (pinfunction "P5.0/A8/VREF+/VeREF+_9") (pintype "input+no_connect"))
    )
    (net (code "66") (name "unconnected-(U1-P5.1{slash}A9{slash}VREF-{slash}VeREF--Pad10)") (class "Default")
      (node (ref "U1") (pin "10") (pinfunction "P5.1/A9/VREF-/VeREF-_10") (pintype "input+no_connect"))
    )
    (net (code "67") (name "unconnected-(U1-P5.4{slash}XIN-Pad12)") (class "Default")
      (node (ref "U1") (pin "12") (pinfunction "P5.4/XIN_12") (pintype "input+no_connect"))
    )
    (net (code "68") (name "unconnected-(U1-P5.5{slash}XOUT-Pad13)") (class "Default")
      (node (ref "U1") (pin "13") (pinfunction "P5.5/XOUT_13") (pintype "input+no_connect"))
    )
    (net (code "69") (name "unconnected-(U1-P5.6{slash}TB0.0-Pad55)") (class "Default")
      (node (ref "U1") (pin "55") (pinfunction "P5.6/TB0.0_55") (pintype "input+no_connect"))
    )
    (net (code "70") (name "unconnected-(U1-P5.7{slash}TB0.1-Pad56)") (class "Default")
      (node (ref "U1") (pin "56") (pinfunction "P5.7/TB0.1_56") (pintype "input+no_connect"))
    )
    (net (code "71") (name "unconnected-(U1-P6.0{slash}CB0{slash}A0-Pad77)") (class "Default")
      (node (ref "U1") (pin "77") (pinfunction "P6.0/CB0/A0_77") (pintype "input+no_connect"))
    )
    (net (code "72") (name "unconnected-(U1-P6.1{slash}CB1{slash}A1-Pad78)") (class "Default")
      (node (ref "U1") (pin "78") (pinfunction "P6.1/CB1/A1_78") (pintype "input+no_connect"))
    )
    (net (code "73") (name "unconnected-(U1-P6.2{slash}CB2{slash}A2-Pad79)") (class "Default")
      (node (ref "U1") (pin "79") (pinfunction "P6.2/CB2/A2_79") (pintype "input+no_connect"))
    )
    (net (code "74") (name "unconnected-(U1-P6.3{slash}CB3{slash}A3-Pad80)") (class "Default")
      (node (ref "U1") (pin "80") (pinfunction "P6.3/CB3/A3_80") (pintype "input+no_connect"))
    )
    (net (code "75") (name "unconnected-(U1-P6.4{slash}CB4{slash}A4-Pad1)") (class "Default")
      (node (ref "U1") (pin "1") (pinfunction "P6.4/CB4/A4_1") (pintype "input+no_connect"))
    )
    (net (code "76") (name "unconnected-(U1-P6.5{slash}CB5{slash}A5-Pad2)") (class "Default")
      (node (ref "U1") (pin "2") (pinfunction "P6.5/CB5/A5_2") (pintype "input+no_connect"))
    )
    (net (code "77") (name "unconnected-(U1-P6.6{slash}CB6{slash}A6-Pad3)") (class "Default")
      (node (ref "U1") (pin "3") (pinfunction "P6.6/CB6/A6_3") (pintype "input+no_connect"))
    )
    (net (code "78") (name "unconnected-(U1-P6.7{slash}CB7{slash}A7-Pad4)") (class "Default")
      (node (ref "U1") (pin "4") (pinfunction "P6.7/CB7/A7_4") (pintype "input+no_connect"))
    )
    (net (code "79") (name "unconnected-(U1-P7.0{slash}CB8{slash}A12-Pad5)") (class "Default")
      (node (ref "U1") (pin "5") (pinfunction "P7.0/CB8/A12_5") (pintype "input+no_connect"))
    )
    (net (code "80") (name "unconnected-(U1-P7.1{slash}CB9{slash}A13-Pad6)") (class "Default")
      (node (ref "U1") (pin "6") (pinfunction "P7.1/CB9/A13_6") (pintype "input+no_connect"))
    )
    (net (code "81") (name "unconnected-(U1-P7.2{slash}CB10{slash}A14-Pad7)") (class "Default")
      (node (ref "U1") (pin "7") (pinfunction "P7.2/CB10/A14_7") (pintype "input+no_connect"))
    )
    (net (code "82") (name "unconnected-(U1-P7.3{slash}CB11{slash}A15-Pad8)") (class "Default")
      (node (ref "U1") (pin "8") (pinfunction "P7.3/CB11/A15_8") (pintype "input+no_connect"))
    )
    (net (code "83") (name "unconnected-(U1-P7.4{slash}TB0.2-Pad57)") (class "Default")
      (node (ref "U1") (pin "57") (pinfunction "P7.4/TB0.2_57") (pintype "input+no_connect"))
    )
    (net (code "84") (name "unconnected-(U1-P7.5{slash}TB0.3-Pad58)") (class "Default")
      (node (ref "U1") (pin "58") (pinfunction "P7.5/TB0.3_58") (pintype "input+no_connect"))
    )
    (net (code "85") (name "unconnected-(U1-P7.6{slash}TB0.4-Pad59)") (class "Default")
      (node (ref "U1") (pin "59") (pinfunction "P7.6/TB0.4_59") (pintype "input+no_connect"))
    )
    (net (code "86") (name "unconnected-(U1-P7.7{slash}TB0CLK{slash}MCLK-Pad60)") (class "Default")
      (node (ref "U1") (pin "60") (pinfunction "P7.7/TB0CLK/MCLK_60") (pintype "input+no_connect"))
    )
    (net (code "87") (name "unconnected-(U1-PJ.0{slash}TDO-Pad72)") (class "Default")
      (node (ref "U1") (pin "72") (pinfunction "PJ.0/TDO_72") (pintype "input+no_connect"))
    )
    (net (code "88") (name "unconnected-(U1-PJ.1{slash}TDI{slash}TCLK-Pad73)") (class "Default")
      (node (ref "U1") (pin "73") (pinfunction "PJ.1/TDI/TCLK_73") (pintype "input+no_connect"))
    )
    (net (code "89") (name "unconnected-(U1-PJ.2{slash}TMS-Pad74)") (class "Default")
      (node (ref "U1") (pin "74") (pinfunction "PJ.2/TMS_74") (pintype "input+no_connect"))
    )
    (net (code "90") (name "unconnected-(U1-PJ.3{slash}TCK-Pad75)") (class "Default")
      (node (ref "U1") (pin "75") (pinfunction "PJ.3/TCK_75") (pintype "input+no_connect"))
    )
    (net (code "91") (name "unconnected-(USB1-CC1-PadA5)") (class "Default")
      (node (ref "USB1") (pin "A5") (pinfunction "CC1_A5") (pintype "input+no_connect"))
    )
    (net (code "92") (name "unconnected-(USB1-CC2-PadB5)") (class "Default")
      (node (ref "USB1") (pin "B5") (pinfunction "CC2_B5") (pintype "input+no_connect"))
    )
    (net (code "93") (name "unconnected-(USB1-SBU1-PadA8)") (class "Default")
      (node (ref "USB1") (pin "A8") (pinfunction "SBU1_A8") (pintype "input+no_connect"))
    )
    (net (code "94") (name "unconnected-(USB1-SBU2-PadB8)") (class "Default")
      (node (ref "USB1") (pin "B8") (pinfunction "SBU2_B8") (pintype "input+no_connect"))
    )
  )
)
